# Ethernet.net
KiCad netlist of a schematic drawn in Altium Designer
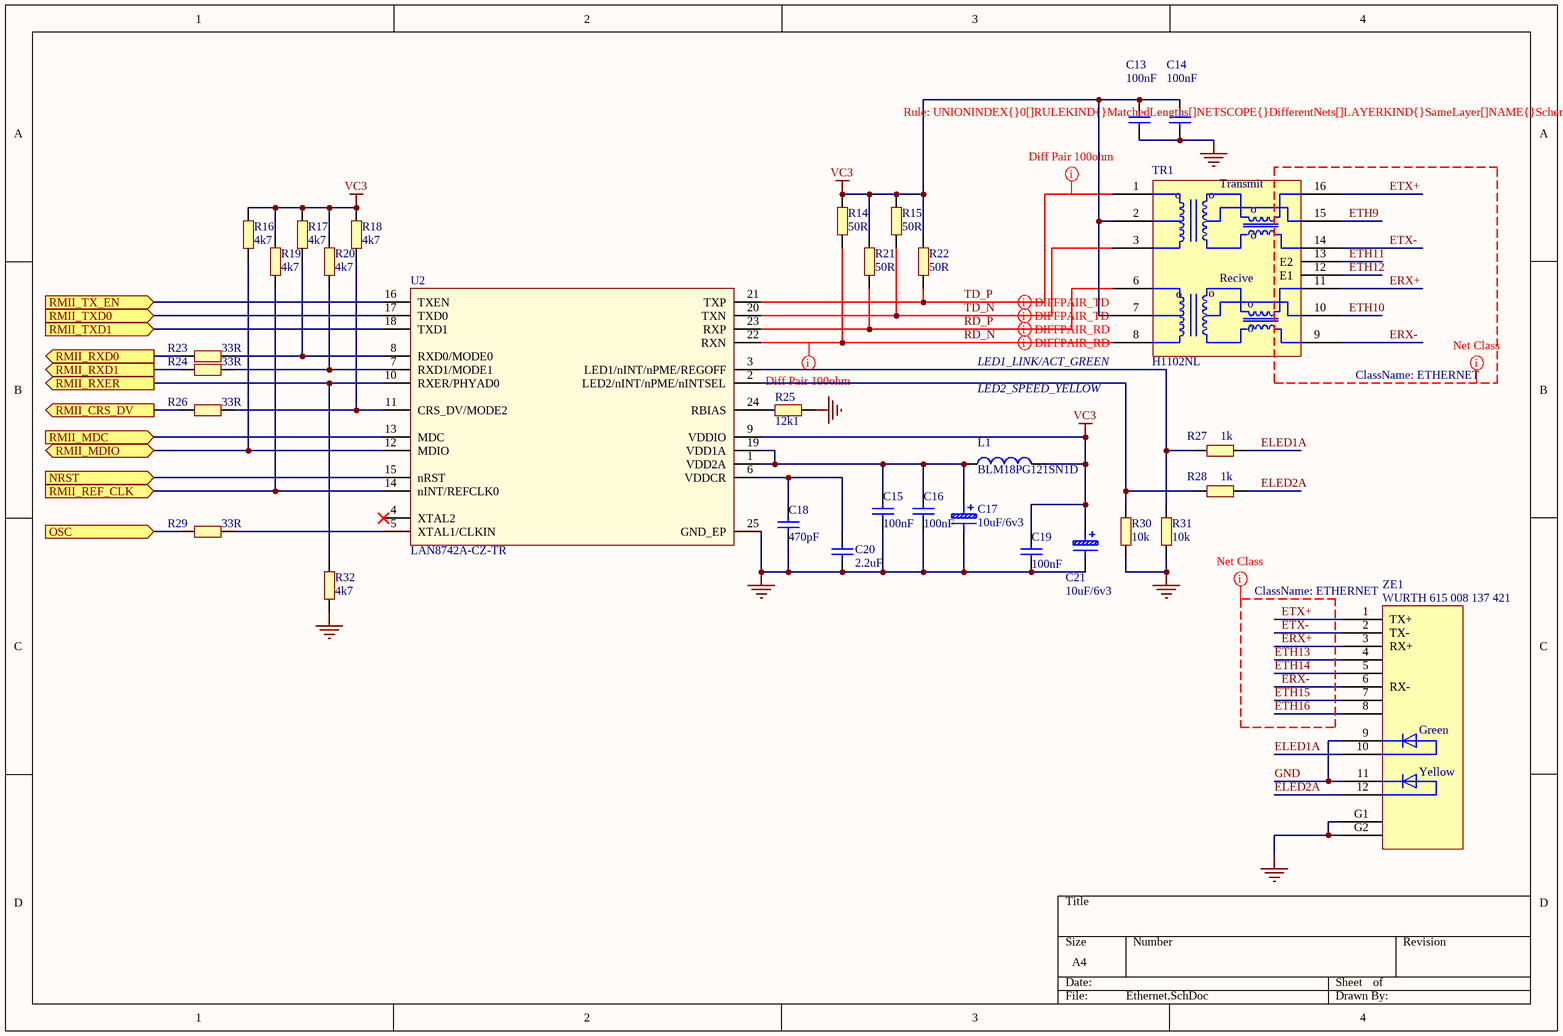
[diagram p0: Ethernet.SchDoc]

(export (version "E")
  (design (tool "Eeschema 10.0.6"))
  (components
    (comp (ref "C13")
      (value "100nF")
      (footprint "0603C")
      (description "Capacitor,100nF,16V,X7R,10%,0402,YAGEO")
      (libsource (lib "MCD_TOOLS") (part "Cap_100nF_X7R_10%_0402"))
    )
    (comp (ref "C14")
      (value "100nF")
      (footprint "0603C")
      (description "Capacitor,100nF,16V,X7R,10%,0402,YAGEO")
      (libsource (lib "MCD_TOOLS") (part "Cap_100nF_X7R_10%_0402"))
    )
    (comp (ref "C15")
      (value "100nF")
      (footprint "0603C")
      (description "Capacitor,100nF,16V,X7R,10%,0402,YAGEO")
      (libsource (lib "MCD_TOOLS") (part "Cap_100nF_X7R_10%_0402"))
    )
    (comp (ref "C16")
      (value "100nF")
      (footprint "0603C")
      (description "Capacitor,100nF,16V,X7R,10%,0402,YAGEO")
      (libsource (lib "MCD_TOOLS") (part "Cap_100nF_X7R_10%_0402"))
    )
    (comp (ref "C17") (value "10uF/6v3") (footprint "CAP_A") (libsource (lib "GkSchlib") (part "CapTantal")))
    (comp (ref "C18")
      (value "470pF")
      (footprint "0603C")
      (description "Capacitor,470pF,16V,X7R,10%,0402,YAGEO")
      (libsource (lib "MCD_TOOLS") (part "Cap_470pF_X7R_10%_0402"))
    )
    (comp (ref "C19")
      (value "100nF")
      (footprint "0603C")
      (description "Capacitor,100nF,16V,X7R,10%,0402,YAGEO")
      (libsource (lib "MCD_TOOLS") (part "Cap_100nF_X7R_10%_0402"))
    )
    (comp (ref "C20")
      (value "2.2uF")
      (footprint "0603C")
      (description "Capacitor,1uF,16V,X5R,10%,0603,YAGEO")
      (libsource (lib "MCD_TOOLS") (part "Cap_1uF_X5R_10%_0603"))
    )
    (comp (ref "C21") (value "10uF/6v3") (footprint "CAP_A") (libsource (lib "GkSchlib") (part "CapTantal")))
    (comp (ref "L1")
      (value "BLM18PG121SN1D")
      (footprint "0603L")
      (description "Bead,120R,2A,0603,BLM18PG121SN1D,MURATA")
      (libsource (lib "MCD_TOOLS") (part "BEAD_120R_2A_0603"))
    )
    (comp (ref "R14") (value "50R") (footprint "0603R") (libsource (lib "") (part "RES3_1")))
    (comp (ref "R15") (value "50R") (footprint "0603R") (libsource (lib "") (part "RES3_1")))
    (comp (ref "R16") (value "4k7") (footprint "0603R") (libsource (lib "") (part "RES3_1")))
    (comp (ref "R17") (value "4k7") (footprint "0603R") (libsource (lib "") (part "RES3_2")))
    (comp (ref "R18") (value "4k7") (footprint "0603R") (libsource (lib "") (part "RES3_2")))
    (comp (ref "R19") (value "4k7") (footprint "0603R") (libsource (lib "") (part "RES3_1")))
    (comp (ref "R20") (value "4k7") (footprint "0603R") (libsource (lib "") (part "RES3_2")))
    (comp (ref "R21") (value "50R") (footprint "0603R") (libsource (lib "") (part "RES3_1")))
    (comp (ref "R22") (value "50R") (footprint "0603R") (libsource (lib "") (part "RES3_1")))
    (comp (ref "R23") (value "33R") (footprint "0603R") (libsource (lib "*") (part "RES3")))
    (comp (ref "R24") (value "33R") (footprint "0603R") (libsource (lib "*") (part "RES3")))
    (comp (ref "R25") (value "12k1") (footprint "0603R") (libsource (lib "") (part "RES3_3")))
    (comp (ref "R26") (value "33R") (footprint "0603R") (libsource (lib "*") (part "RES3")))
    (comp (ref "R27") (value "1k") (footprint "0603R") (libsource (lib "") (part "RES3_3")))
    (comp (ref "R28") (value "1k") (footprint "0603R") (libsource (lib "") (part "RES3_3")))
    (comp (ref "R29") (value "33R") (footprint "0603R") (libsource (lib "*") (part "RES3")))
    (comp (ref "R30") (value "10k") (footprint "0603R") (libsource (lib "") (part "RES3_1")))
    (comp (ref "R31") (value "10k") (footprint "0603R") (libsource (lib "") (part "RES3_1")))
    (comp (ref "R32") (value "4k7") (footprint "0603R") (libsource (lib "") (part "RES3_1")))
    (comp (ref "TR1") (value "H1102NL") (footprint "H1102") (libsource (lib "GkSchlib") (part "H1102NL")))
    (comp (ref "U2")
      (value "LAN8742A-CZ-TR")
      (footprint "QFN24_LAN")
      (libsource (lib "MCD_TOOLS") (part "LAN8742A-CZ-TR"))
    )
    (comp (ref "ZE1")
      (value "WURTH 615 008 137 421")
      (footprint "RJHSE-3381")
      (libsource (lib "*") (part "RJ45GELED"))
    )
  )
  (nets
    (net (code "1") (name "/ELED1A") (class "Default")
      (node (ref "R27") (pin "1") (pintype "passive"))
      (node (ref "ZE1") (pin "10") (pintype "passive"))
    )
    (net (code "2") (name "/ELED2A") (class "Default")
      (node (ref "R28") (pin "1") (pintype "passive"))
      (node (ref "ZE1") (pin "12") (pintype "passive"))
    )
    (net (code "3") (name "/ERX+") (class "Default")
      (node (ref "TR1") (pin "11") (pinfunction "RO1_11") (pintype "passive"))
      (node (ref "ZE1") (pin "3") (pinfunction "RX+_3") (pintype "passive"))
    )
    (net (code "4") (name "/ERX-") (class "Default")
      (node (ref "TR1") (pin "9") (pinfunction "RO2_9") (pintype "passive"))
      (node (ref "ZE1") (pin "6") (pinfunction "RX-_6") (pintype "passive"))
    )
    (net (code "5") (name "/ETH9") (class "Default") (node (ref "TR1") (pin "15") (pintype "passive")))
    (net (code "6") (name "/ETH10") (class "Default") (node (ref "TR1") (pin "10") (pintype "passive")))
    (net (code "7") (name "/ETH11") (class "Default")
      (node (ref "TR1") (pin "13") (pinfunction "E2_13") (pintype "passive"))
    )
    (net (code "8") (name "/ETH12") (class "Default")
      (node (ref "TR1") (pin "12") (pinfunction "E1_12") (pintype "passive"))
    )
    (net (code "9") (name "/ETH13") (class "Default") (node (ref "ZE1") (pin "4") (pintype "passive")))
    (net (code "10") (name "/ETH14") (class "Default") (node (ref "ZE1") (pin "5") (pintype "passive")))
    (net (code "11") (name "/ETH15") (class "Default") (node (ref "ZE1") (pin "7") (pintype "passive")))
    (net (code "12") (name "/ETH16") (class "Default") (node (ref "ZE1") (pin "8") (pintype "passive")))
    (net (code "13") (name "/ETX+") (class "Default")
      (node (ref "TR1") (pin "16") (pinfunction "TO1_16") (pintype "passive"))
      (node (ref "ZE1") (pin "1") (pinfunction "TX+_1") (pintype "passive"))
    )
    (net (code "14") (name "/ETX-") (class "Default")
      (node (ref "TR1") (pin "14") (pinfunction "TO2_14") (pintype "passive"))
      (node (ref "ZE1") (pin "2") (pinfunction "TX-_2") (pintype "passive"))
    )
    (net (code "15") (name "/NRST") (class "Default")
      (node (ref "U2") (pin "15") (pinfunction "nRST_15") (pintype "passive"))
    )
    (net (code "16") (name "/OSC") (class "Default") (node (ref "R29") (pin "1") (pintype "passive")))
    (net (code "17") (name "/RD_N") (class "Default")
      (node (ref "R14") (pin "1") (pintype "passive"))
      (node (ref "TR1") (pin "8") (pinfunction "RI3_8") (pintype "passive"))
      (node (ref "U2") (pin "22") (pinfunction "RXN_22") (pintype "passive"))
    )
    (net (code "18") (name "/RD_P") (class "Default")
      (node (ref "R21") (pin "1") (pintype "passive"))
      (node (ref "TR1") (pin "6") (pinfunction "RI1_6") (pintype "passive"))
      (node (ref "U2") (pin "23") (pinfunction "RXP_23") (pintype "passive"))
    )
    (net (code "19") (name "/RMII_CRS_DV") (class "Default") (node (ref "R26") (pin "1") (pintype "passive")))
    (net (code "20") (name "/RMII_MDC") (class "Default")
      (node (ref "U2") (pin "13") (pinfunction "MDC_13") (pintype "passive"))
    )
    (net (code "21") (name "/RMII_MDIO") (class "Default")
      (node (ref "R16") (pin "1") (pintype "passive"))
      (node (ref "U2") (pin "12") (pinfunction "MDIO_12") (pintype "passive"))
    )
    (net (code "22") (name "/RMII_REF_CLK") (class "Default")
      (node (ref "R19") (pin "1") (pintype "passive"))
      (node (ref "U2") (pin "14") (pinfunction "nINT/REFCLK0_14") (pintype "passive"))
    )
    (net (code "23") (name "/RMII_RXD0") (class "Default") (node (ref "R23") (pin "1") (pintype "passive")))
    (net (code "24") (name "/RMII_RXD1") (class "Default") (node (ref "R24") (pin "1") (pintype "passive")))
    (net (code "25") (name "/RMII_RXER") (class "Default")
      (node (ref "R32") (pin "2") (pintype "passive"))
      (node (ref "U2") (pin "10") (pinfunction "RXER/PHYAD0_10") (pintype "passive"))
    )
    (net (code "26") (name "/RMII_TXD0") (class "Default")
      (node (ref "U2") (pin "17") (pinfunction "TXD0_17") (pintype "passive"))
    )
    (net (code "27") (name "/RMII_TXD1") (class "Default")
      (node (ref "U2") (pin "18") (pinfunction "TXD1_18") (pintype "passive"))
    )
    (net (code "28") (name "/RMII_TX_EN") (class "Default")
      (node (ref "U2") (pin "16") (pinfunction "TXEN_16") (pintype "passive"))
    )
    (net (code "29") (name "/TD_N") (class "Default")
      (node (ref "R15") (pin "1") (pintype "passive"))
      (node (ref "TR1") (pin "3") (pinfunction "TI3_3") (pintype "passive"))
      (node (ref "U2") (pin "20") (pinfunction "TXN_20") (pintype "passive"))
    )
    (net (code "30") (name "/TD_P") (class "Default")
      (node (ref "R22") (pin "1") (pintype "passive"))
      (node (ref "TR1") (pin "1") (pinfunction "TI1_1") (pintype "passive"))
      (node (ref "U2") (pin "21") (pinfunction "TXP_21") (pintype "passive"))
    )
    (net (code "31") (name "GND") (class "Default")
      (node (ref "C13") (pin "1") (pinfunction "1_1") (pintype "passive"))
      (node (ref "C14") (pin "1") (pinfunction "1_1") (pintype "passive"))
      (node (ref "C15") (pin "1") (pinfunction "1_1") (pintype "passive"))
      (node (ref "C16") (pin "1") (pinfunction "1_1") (pintype "passive"))
      (node (ref "C17") (pin "1") (pintype "passive"))
      (node (ref "C18") (pin "1") (pinfunction "1_1") (pintype "passive"))
      (node (ref "C19") (pin "1") (pinfunction "1_1") (pintype "passive"))
      (node (ref "C20") (pin "1") (pinfunction "1_1") (pintype "passive"))
      (node (ref "C21") (pin "1") (pintype "passive"))
      (node (ref "R25") (pin "1") (pintype "passive"))
      (node (ref "R30") (pin "1") (pintype "passive"))
      (node (ref "R31") (pin "1") (pintype "passive"))
      (node (ref "R32") (pin "1") (pintype "passive"))
      (node (ref "U2") (pin "25") (pinfunction "GND_EP_25") (pintype "passive"))
      (node (ref "ZE1") (pin "11") (pintype "passive"))
      (node (ref "ZE1") (pin "9") (pintype "passive"))
      (node (ref "ZE1") (pin "G1") (pintype "passive"))
      (node (ref "ZE1") (pin "G2") (pintype "passive"))
    )
    (net (code "32") (name "Net-(U2-CRS_DV{slash}MODE2)") (class "Default")
      (node (ref "R18") (pin "2") (pintype "passive"))
      (node (ref "R26") (pin "2") (pintype "passive"))
      (node (ref "U2") (pin "11") (pinfunction "CRS_DV/MODE2_11") (pintype "passive"))
    )
    (net (code "33") (name "Net-(U2-LED1{slash}nINT{slash}nPME{slash}REGOFF)") (class "Default")
      (node (ref "R27") (pin "2") (pintype "passive"))
      (node (ref "R31") (pin "2") (pintype "passive"))
      (node (ref "U2") (pin "3") (pinfunction "LED1/nINT/nPME/REGOFF_3") (pintype "passive"))
    )
    (net (code "34") (name "Net-(U2-LED2{slash}nINT{slash}nPME{slash}nINTSEL)") (class "Default")
      (node (ref "R28") (pin "2") (pintype "passive"))
      (node (ref "R30") (pin "2") (pintype "passive"))
      (node (ref "U2") (pin "2") (pinfunction "LED2/nINT/nPME/nINTSEL_2") (pintype "passive"))
    )
    (net (code "35") (name "Net-(U2-RBIAS)") (class "Default")
      (node (ref "R25") (pin "2") (pintype "passive"))
      (node (ref "U2") (pin "24") (pinfunction "RBIAS_24") (pintype "passive"))
    )
    (net (code "36") (name "Net-(U2-RXD0{slash}MODE0)") (class "Default")
      (node (ref "R17") (pin "2") (pintype "passive"))
      (node (ref "R23") (pin "2") (pintype "passive"))
      (node (ref "U2") (pin "8") (pinfunction "RXD0/MODE0_8") (pintype "passive"))
    )
    (net (code "37") (name "Net-(U2-RXD1{slash}MODE1)") (class "Default")
      (node (ref "R20") (pin "2") (pintype "passive"))
      (node (ref "R24") (pin "2") (pintype "passive"))
      (node (ref "U2") (pin "7") (pinfunction "RXD1/MODE1_7") (pintype "passive"))
    )
    (net (code "38") (name "Net-(U2-VDD1A)") (class "Default")
      (node (ref "C15") (pin "2") (pinfunction "2_2") (pintype "passive"))
      (node (ref "C16") (pin "2") (pinfunction "2_2") (pintype "passive"))
      (node (ref "C17") (pin "2") (pintype "passive"))
      (node (ref "L1") (pin "1") (pinfunction "1_1") (pintype "passive"))
      (node (ref "U2") (pin "1") (pinfunction "VDD2A_1") (pintype "passive"))
      (node (ref "U2") (pin "19") (pinfunction "VDD1A_19") (pintype "passive"))
    )
    (net (code "39") (name "Net-(U2-VDDCR)") (class "Default")
      (node (ref "C18") (pin "2") (pinfunction "2_2") (pintype "passive"))
      (node (ref "C20") (pin "2") (pinfunction "2_2") (pintype "passive"))
      (node (ref "U2") (pin "6") (pinfunction "VDDCR_6") (pintype "passive"))
    )
    (net (code "40") (name "Net-(U2-XTAL1{slash}CLKIN)") (class "Default")
      (node (ref "R29") (pin "2") (pintype "passive"))
      (node (ref "U2") (pin "5") (pinfunction "XTAL1/CLKIN_5") (pintype "passive"))
    )
    (net (code "41") (name "VC3") (class "Default")
      (node (ref "C13") (pin "2") (pinfunction "2_2") (pintype "passive"))
      (node (ref "C14") (pin "2") (pinfunction "2_2") (pintype "passive"))
      (node (ref "C19") (pin "2") (pinfunction "2_2") (pintype "passive"))
      (node (ref "C21") (pin "2") (pintype "passive"))
      (node (ref "L1") (pin "2") (pinfunction "2_2") (pintype "passive"))
      (node (ref "R14") (pin "2") (pintype "passive"))
      (node (ref "R15") (pin "2") (pintype "passive"))
      (node (ref "R16") (pin "2") (pintype "passive"))
      (node (ref "R17") (pin "1") (pintype "passive"))
      (node (ref "R18") (pin "1") (pintype "passive"))
      (node (ref "R19") (pin "2") (pintype "passive"))
      (node (ref "R20") (pin "1") (pintype "passive"))
      (node (ref "R21") (pin "2") (pintype "passive"))
      (node (ref "R22") (pin "2") (pintype "passive"))
      (node (ref "TR1") (pin "2") (pinfunction "TI2_2") (pintype "passive"))
      (node (ref "TR1") (pin "7") (pinfunction "RI2_7") (pintype "passive"))
      (node (ref "U2") (pin "9") (pinfunction "VDDIO_9") (pintype "passive"))
    )
    (net (code "42") (name "unconnected-(U2-XTAL2-Pad4)") (class "Default")
      (node (ref "U2") (pin "4") (pinfunction "XTAL2_4") (pintype "passive+no_connect"))
    )
  )
)
